# Schematic.net
KiCad netlist of a schematic drawn in Altium Designer
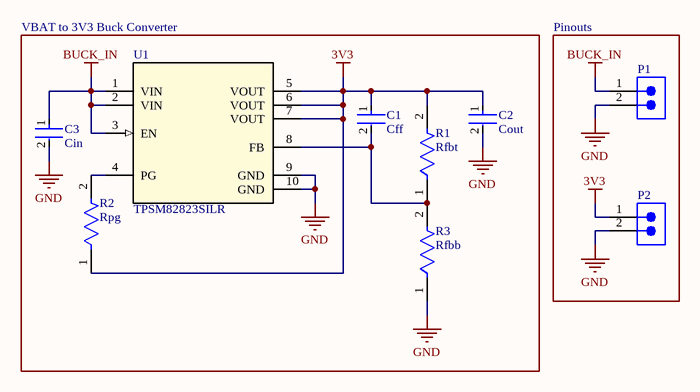
[diagram p0: Schematic.SchDoc]

(export (version "E")
  (design (tool "Eeschema 10.0.6"))
  (components
    (comp (ref "C1")
      (value "Cff")
      (footprint "FP-GRM033-0_03-IPC_A")
      (description "Chip Multilayer Ceramic Capacitors for General Purpose, 0201, 120pF, X7R, 15%, 10%, 25V")
      (fields (field (name "TOLERANCE") "10%"))
      (libsource (lib "Altium Content Vault") (part "b4654b650e69147ec39a6b967a45e02"))
    )
    (comp (ref "C2")
      (value "Cout")
      (footprint "FP-C0805C-DG-MFG")
      (description "CAP CER 10UF 10V X5R 0805")
      (fields (field (name "TOLERANCE") "10%") (field (name "MANUFACTURER PART NUMBER") "C0805C106K8PACTU"))
      (libsource (lib "Altium Content Vault") (part "11868f565c42a9108669ba33697ecf6"))
    )
    (comp (ref "C3")
      (value "Cin")
      (footprint "FP-GRM188-0_1-e0_2_0_55-IPC_A")
      (description "Chip Multilayer Ceramic Capacitors for General Purpose, 0603, 10uF, X5R, 15%, 20%, 6.3V")
      (fields (field (name "VOLTAGE") "6.3V") (field (name "TOLERANCE") "20%"))
      (libsource (lib "Altium Content Vault") (part "02cd4be3c70576c341d710602a673aa"))
    )
    (comp (ref "P1")
      (value "61300211121")
      (footprint "61300211121")
      (libsource (lib "Altium Content Vault") (part "Header_Male_1R_02P"))
    )
    (comp (ref "P2")
      (value "61300211121")
      (footprint "61300211121")
      (libsource (lib "Altium Content Vault") (part "Header_Male_1R_02P"))
    )
    (comp (ref "R1")
      (value "Rfbt")
      (footprint "FP-CRCW0402-e3-MFG")
      (description "RES Thick Film, 453kΩ, 1%, 0.063W, 100ppm/°C, 0402")
      (fields (field (name "TOLERANCE") "1%"))
      (libsource (lib "Altium Content Vault") (part "1029c3af85768c4190bb7ad29bc67b5"))
    )
    (comp (ref "R2")
      (value "Rpg")
      (footprint "FP-CRCW0402-e3-IPC_C")
      (description "RES Thick Film, 100kΩ, 1%, 0.063W, 100ppm/°C, 0402")
      (fields (field (name "TOLERANCE") "1%"))
      (libsource (lib "Altium Content Vault") (part "1029c3af85768c4190bb7ad29bc67b5"))
    )
    (comp (ref "R3")
      (value "Rfbb")
      (footprint "FP-CRCW0402-e3-IPC_C")
      (description "RES Thick Film, 100kΩ, 1%, 0.063W, 100ppm/°C, 0402")
      (fields (field (name "TOLERANCE") "1%"))
      (libsource (lib "Altium Content Vault") (part "1029c3af85768c4190bb7ad29bc67b5"))
    )
    (comp (ref "U1")
      (value "TPSM82823SILR")
      (footprint "SIL0010D-MFG")
      (description "No Description Available")
      (libsource (lib "TPSM82823SILR") (part "TPSM82823SILR"))
    )
  )
  (nets
    (net (code "1") (name "3V3") (class "Default")
      (node (ref "C1") (pin "1") (pinfunction "1_1") (pintype "passive"))
      (node (ref "C2") (pin "1") (pinfunction "1_1") (pintype "passive"))
      (node (ref "P2") (pin "1") (pinfunction "1_1") (pintype "passive"))
      (node (ref "R1") (pin "2") (pinfunction "2_2") (pintype "passive"))
      (node (ref "R2") (pin "1") (pinfunction "1_1") (pintype "passive"))
      (node (ref "U1") (pin "5") (pinfunction "VOUT_5") (pintype "power_in"))
      (node (ref "U1") (pin "6") (pinfunction "VOUT_6") (pintype "power_in"))
      (node (ref "U1") (pin "7") (pinfunction "VOUT_7") (pintype "power_in"))
    )
    (net (code "2") (name "BUCK_IN") (class "Default")
      (node (ref "C3") (pin "1") (pinfunction "1_1") (pintype "passive"))
      (node (ref "P1") (pin "1") (pinfunction "1_1") (pintype "passive"))
      (node (ref "U1") (pin "1") (pinfunction "VIN_1") (pintype "power_in"))
      (node (ref "U1") (pin "2") (pinfunction "VIN_2") (pintype "power_in"))
      (node (ref "U1") (pin "3") (pinfunction "EN_3") (pintype "input"))
    )
    (net (code "3") (name "GND") (class "Default")
      (node (ref "C2") (pin "2") (pinfunction "2_2") (pintype "passive"))
      (node (ref "C3") (pin "2") (pinfunction "2_2") (pintype "passive"))
      (node (ref "P1") (pin "2") (pinfunction "2_2") (pintype "passive"))
      (node (ref "P2") (pin "2") (pinfunction "2_2") (pintype "passive"))
      (node (ref "R3") (pin "1") (pinfunction "1_1") (pintype "passive"))
      (node (ref "U1") (pin "10") (pinfunction "GND_10") (pintype "power_in"))
      (node (ref "U1") (pin "9") (pinfunction "GND_9") (pintype "power_in"))
    )
    (net (code "4") (name "Net-(U1-FB)") (class "Default")
      (node (ref "C1") (pin "2") (pinfunction "2_2") (pintype "passive"))
      (node (ref "R1") (pin "1") (pinfunction "1_1") (pintype "passive"))
      (node (ref "R3") (pin "2") (pinfunction "2_2") (pintype "passive"))
      (node (ref "U1") (pin "8") (pinfunction "FB_8") (pintype "passive"))
    )
    (net (code "5") (name "Net-(U1-PG)") (class "Default")
      (node (ref "R2") (pin "2") (pinfunction "2_2") (pintype "passive"))
      (node (ref "U1") (pin "4") (pinfunction "PG_4") (pintype "open_collector"))
    )
  )
)
